# 5transistor.net
KiCad netlist of a schematic drawn in EAGLE
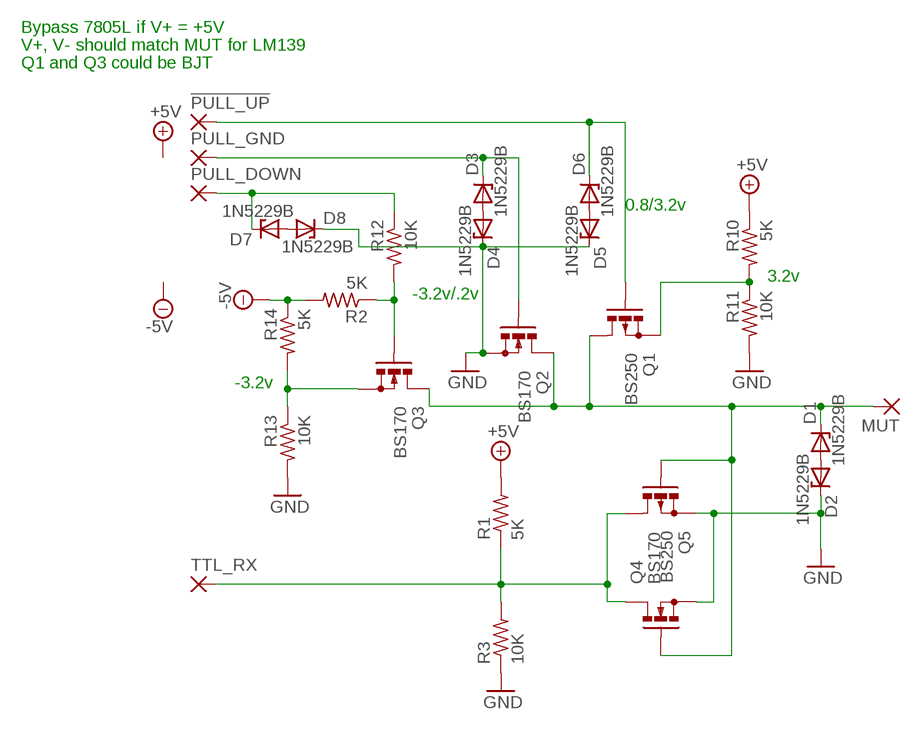
[diagram p0: schematic, sheet 1]

(export (version "E")
  (design (tool "Eeschema 10.0.6"))
  (components
    (comp (ref "!PULL_UP")
      (value "1,6/0,9")
      (footprint "eagle-import:1,6_0,9")
      (libsource (lib "eagle-import") (part "1,6/0,9"))
    )
    (comp (ref "D1")
      (value "1N5229B")
      (footprint "eagle-import:ZDIO-2.5")
      (libsource (lib "eagle-import") (part "ZENER-DIODEZD-2.5"))
    )
    (comp (ref "D2")
      (value "1N5229B")
      (footprint "eagle-import:ZDIO-2.5")
      (libsource (lib "eagle-import") (part "ZENER-DIODEZD-2.5"))
    )
    (comp (ref "D3")
      (value "1N5229B")
      (footprint "eagle-import:ZDIO-2.5")
      (libsource (lib "eagle-import") (part "ZENER-DIODEZD-2.5"))
    )
    (comp (ref "D4")
      (value "1N5229B")
      (footprint "eagle-import:ZDIO-2.5")
      (libsource (lib "eagle-import") (part "ZENER-DIODEZD-2.5"))
    )
    (comp (ref "D5")
      (value "1N5229B")
      (footprint "eagle-import:ZDIO-2.5")
      (libsource (lib "eagle-import") (part "ZENER-DIODEZD-2.5"))
    )
    (comp (ref "D6")
      (value "1N5229B")
      (footprint "eagle-import:ZDIO-2.5")
      (libsource (lib "eagle-import") (part "ZENER-DIODEZD-2.5"))
    )
    (comp (ref "D7")
      (value "1N5229B")
      (footprint "eagle-import:ZDIO-2.5")
      (libsource (lib "eagle-import") (part "ZENER-DIODEZD-2.5"))
    )
    (comp (ref "D8")
      (value "1N5229B")
      (footprint "eagle-import:ZDIO-2.5")
      (libsource (lib "eagle-import") (part "ZENER-DIODEZD-2.5"))
    )
    (comp (ref "MUT")
      (value "1,6/0,9")
      (footprint "eagle-import:1,6_0,9")
      (libsource (lib "eagle-import") (part "1,6/0,9"))
    )
    (comp (ref "PULL_DOWN")
      (value "1,6/0,9")
      (footprint "eagle-import:1,6_0,9")
      (libsource (lib "eagle-import") (part "1,6/0,9"))
    )
    (comp (ref "PULL_GND")
      (value "1,6/0,9")
      (footprint "eagle-import:1,6_0,9")
      (libsource (lib "eagle-import") (part "1,6/0,9"))
    )
    (comp (ref "Q1")
      (value "BS250")
      (footprint "eagle-import:SOT54E")
      (libsource (lib "eagle-import") (part "BS250"))
    )
    (comp (ref "Q2")
      (value "BS170")
      (footprint "eagle-import:SOT54E")
      (libsource (lib "eagle-import") (part "BS170"))
    )
    (comp (ref "Q3")
      (value "BS170")
      (footprint "eagle-import:SOT54E")
      (libsource (lib "eagle-import") (part "BS170"))
    )
    (comp (ref "Q4")
      (value "BS170")
      (footprint "eagle-import:SOT54E")
      (libsource (lib "eagle-import") (part "BS170"))
    )
    (comp (ref "Q5")
      (value "BS250")
      (footprint "eagle-import:SOT54E")
      (libsource (lib "eagle-import") (part "BS250"))
    )
    (comp (ref "R1")
      (value "5K")
      (footprint "eagle-import:0207_2V")
      (libsource (lib "eagle-import") (part "R-US_0207/2V"))
    )
    (comp (ref "R2")
      (value "5K")
      (footprint "eagle-import:0207_2V")
      (libsource (lib "eagle-import") (part "R-US_0207/2V"))
    )
    (comp (ref "R3")
      (value "10K")
      (footprint "eagle-import:0207_2V")
      (libsource (lib "eagle-import") (part "R-US_0207/2V"))
    )
    (comp (ref "R10")
      (value "5K")
      (footprint "eagle-import:0207_2V")
      (libsource (lib "eagle-import") (part "R-US_0207/2V"))
    )
    (comp (ref "R11")
      (value "10K")
      (footprint "eagle-import:0207_2V")
      (libsource (lib "eagle-import") (part "R-US_0207/2V"))
    )
    (comp (ref "R12")
      (value "10K")
      (footprint "eagle-import:0207_2V")
      (libsource (lib "eagle-import") (part "R-US_0207/2V"))
    )
    (comp (ref "R13")
      (value "10K")
      (footprint "eagle-import:0207_2V")
      (libsource (lib "eagle-import") (part "R-US_0207/2V"))
    )
    (comp (ref "R14")
      (value "5K")
      (footprint "eagle-import:0207_2V")
      (libsource (lib "eagle-import") (part "R-US_0207/2V"))
    )
    (comp (ref "TTL_RX")
      (value "1,6/0,9")
      (footprint "eagle-import:1,6_0,9")
      (libsource (lib "eagle-import") (part "1,6/0,9"))
    )
  )
  (nets
    (net (code "1") (name "+5V") (class "Default")
      (node (ref "R1") (pin "2") (pinfunction "2_2") (pintype "passive"))
      (node (ref "R10") (pin "1") (pinfunction "1_1") (pintype "passive"))
    )
    (net (code "2") (name "-5V") (class "Default")
      (node (ref "R14") (pin "1") (pinfunction "1_1") (pintype "passive"))
      (node (ref "R2") (pin "2") (pinfunction "2_2") (pintype "passive"))
    )
    (net (code "3") (name "GND") (class "Default")
      (node (ref "D2") (pin "C") (pinfunction "C_C") (pintype "passive"))
      (node (ref "D4") (pin "C") (pinfunction "C_C") (pintype "passive"))
      (node (ref "D5") (pin "C") (pinfunction "C_C") (pintype "passive"))
      (node (ref "D8") (pin "C") (pinfunction "C_C") (pintype "passive"))
      (node (ref "Q2") (pin "S") (pinfunction "S_S") (pintype "passive"))
      (node (ref "Q4") (pin "S") (pinfunction "S_S") (pintype "passive"))
      (node (ref "Q5") (pin "S") (pinfunction "S_S") (pintype "passive"))
      (node (ref "R11") (pin "2") (pinfunction "2_2") (pintype "passive"))
      (node (ref "R13") (pin "2") (pinfunction "2_2") (pintype "passive"))
      (node (ref "R3") (pin "1") (pinfunction "1_1") (pintype "passive"))
    )
    (net (code "4") (name "Net-(!PULL_UP-P)") (class "Default")
      (node (ref "!PULL_UP") (pin "1") (pinfunction "P_1") (pintype "passive"))
      (node (ref "D6") (pin "C") (pinfunction "C_C") (pintype "passive"))
      (node (ref "Q1") (pin "G") (pinfunction "G_G") (pintype "passive"))
    )
    (net (code "5") (name "Net-(D1-PadA)") (class "Default")
      (node (ref "D1") (pin "A") (pinfunction "A_A") (pintype "passive"))
      (node (ref "D2") (pin "A") (pinfunction "A_A") (pintype "passive"))
    )
    (net (code "6") (name "Net-(D3-PadA)") (class "Default")
      (node (ref "D3") (pin "A") (pinfunction "A_A") (pintype "passive"))
      (node (ref "D4") (pin "A") (pinfunction "A_A") (pintype "passive"))
    )
    (net (code "7") (name "Net-(D5-PadA)") (class "Default")
      (node (ref "D5") (pin "A") (pinfunction "A_A") (pintype "passive"))
      (node (ref "D6") (pin "A") (pinfunction "A_A") (pintype "passive"))
    )
    (net (code "8") (name "Net-(D7-PadA)") (class "Default")
      (node (ref "D7") (pin "A") (pinfunction "A_A") (pintype "passive"))
      (node (ref "D8") (pin "A") (pinfunction "A_A") (pintype "passive"))
    )
    (net (code "9") (name "Net-(MUT-P)") (class "Default")
      (node (ref "D1") (pin "C") (pinfunction "C_C") (pintype "passive"))
      (node (ref "MUT") (pin "1") (pinfunction "P_1") (pintype "passive"))
      (node (ref "Q1") (pin "D") (pinfunction "D_D") (pintype "passive"))
      (node (ref "Q2") (pin "D") (pinfunction "D_D") (pintype "passive"))
      (node (ref "Q3") (pin "D") (pinfunction "D_D") (pintype "passive"))
      (node (ref "Q4") (pin "G") (pinfunction "G_G") (pintype "passive"))
      (node (ref "Q5") (pin "G") (pinfunction "G_G") (pintype "passive"))
    )
    (net (code "10") (name "Net-(PULL_DOWN-P)") (class "Default")
      (node (ref "D7") (pin "C") (pinfunction "C_C") (pintype "passive"))
      (node (ref "PULL_DOWN") (pin "1") (pinfunction "P_1") (pintype "passive"))
      (node (ref "R12") (pin "1") (pinfunction "1_1") (pintype "passive"))
    )
    (net (code "11") (name "Net-(PULL_GND-P)") (class "Default")
      (node (ref "D3") (pin "C") (pinfunction "C_C") (pintype "passive"))
      (node (ref "PULL_GND") (pin "1") (pinfunction "P_1") (pintype "passive"))
      (node (ref "Q2") (pin "G") (pinfunction "G_G") (pintype "passive"))
    )
    (net (code "12") (name "Net-(Q1-PadS)") (class "Default")
      (node (ref "Q1") (pin "S") (pinfunction "S_S") (pintype "passive"))
      (node (ref "R10") (pin "2") (pinfunction "2_2") (pintype "passive"))
      (node (ref "R11") (pin "1") (pinfunction "1_1") (pintype "passive"))
    )
    (net (code "13") (name "Net-(Q3-PadG)") (class "Default")
      (node (ref "Q3") (pin "G") (pinfunction "G_G") (pintype "passive"))
      (node (ref "R12") (pin "2") (pinfunction "2_2") (pintype "passive"))
      (node (ref "R2") (pin "1") (pinfunction "1_1") (pintype "passive"))
    )
    (net (code "14") (name "Net-(Q3-PadS)") (class "Default")
      (node (ref "Q3") (pin "S") (pinfunction "S_S") (pintype "passive"))
      (node (ref "R13") (pin "1") (pinfunction "1_1") (pintype "passive"))
      (node (ref "R14") (pin "2") (pinfunction "2_2") (pintype "passive"))
    )
    (net (code "15") (name "Net-(TTL_RX-P)") (class "Default")
      (node (ref "Q4") (pin "D") (pinfunction "D_D") (pintype "passive"))
      (node (ref "Q5") (pin "D") (pinfunction "D_D") (pintype "passive"))
      (node (ref "R1") (pin "1") (pinfunction "1_1") (pintype "passive"))
      (node (ref "R3") (pin "2") (pinfunction "2_2") (pintype "passive"))
      (node (ref "TTL_RX") (pin "1") (pinfunction "P_1") (pintype "passive"))
    )
  )
)
